# mcu.net
KiCad netlist of a schematic drawn in Altium Designer
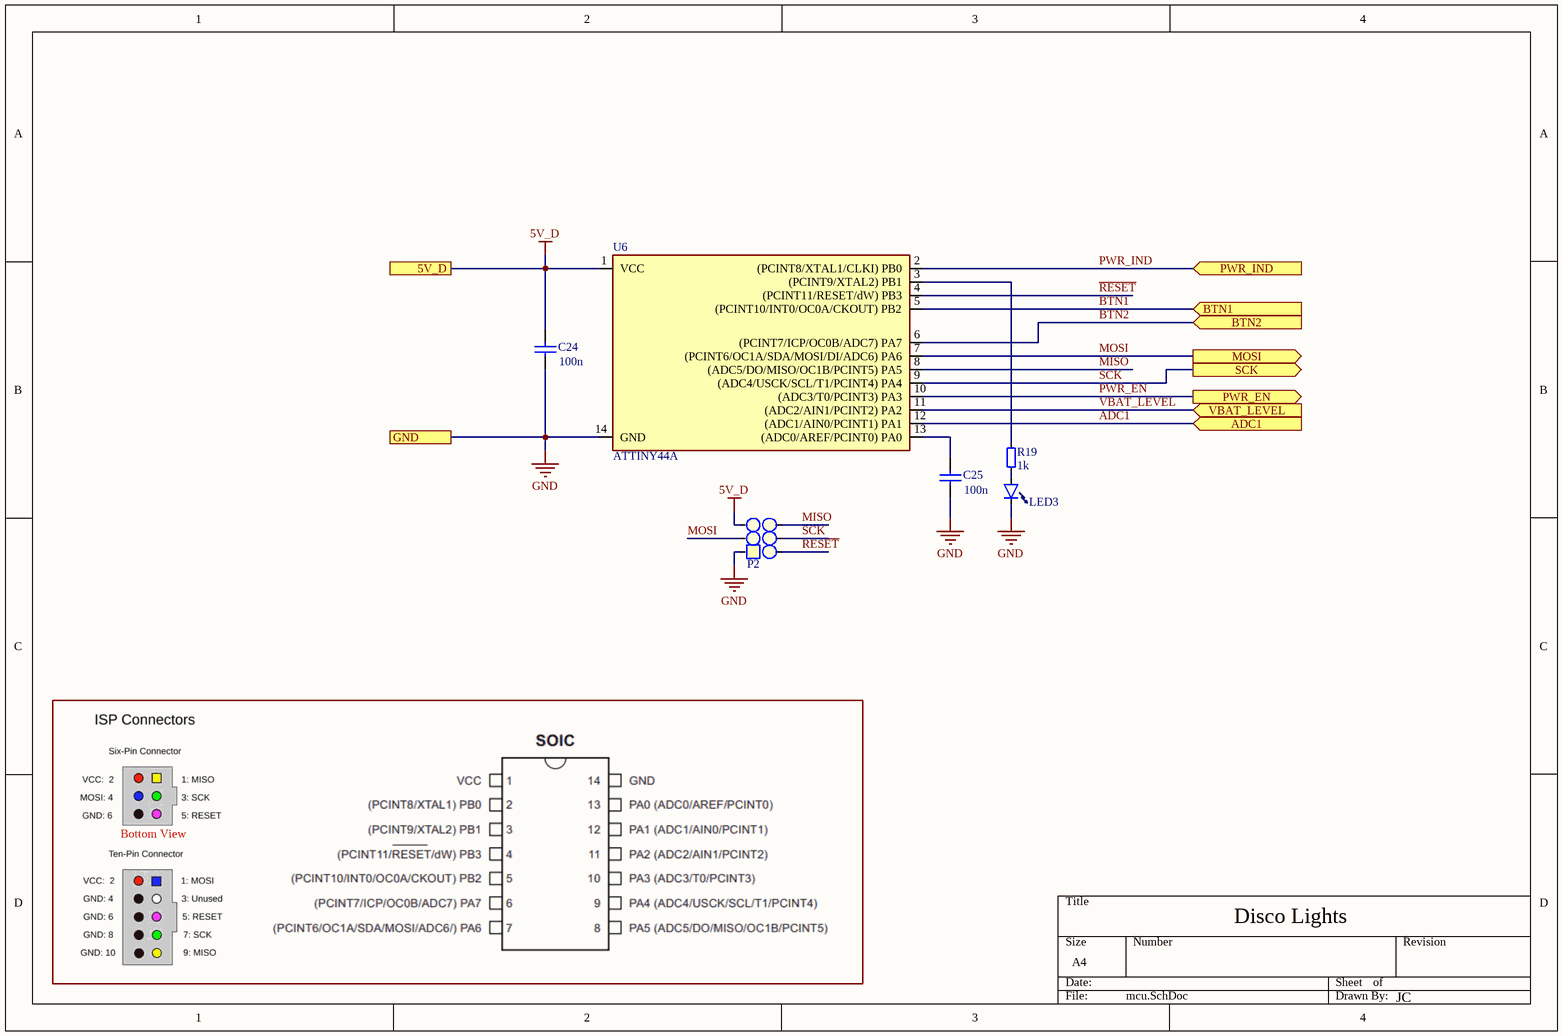
[diagram p0: mcu.SchDoc]

(export (version "E")
  (design (tool "Eeschema 10.0.6"))
  (components
    (comp (ref "C24")
      (value "100n")
      (footprint "MMK7.5104K100K00L4BULK")
      (fields (field (name "Comment") "CAP, TH"))
      (libsource (lib "urad") (part "CAP, TH"))
    )
    (comp (ref "C25")
      (value "100n")
      (footprint "MMK7.5104K100K00L4BULK")
      (fields (field (name "Comment") "CAP, TH"))
      (libsource (lib "urad") (part "CAP, TH"))
    )
    (comp (ref "LED3")
      (value "0805, LED")
      (footprint "0805_led")
      (fields
        (field (name "JLCPCB PART #") "C598285")
        (field (name "MANUFACTURER PART NUMBER") "KP-2012SURCK")
      )
      (libsource (lib "jclib") (part "0805, LED"))
    )
    (comp (ref "P2")
      (value "2x3 Pin Header")
      (footprint "2x3 PH")
      (libsource (lib "jclib") (part "2x3 Pin Header"))
    )
    (comp (ref "R19")
      (value "1k")
      (footprint "0603")
      (fields
        (field (name "JLCPCB PART #") "C203217")
        (field (name "MANUFACTURER PART NUMBER") "CR0603-FX-1001ELF")
        (field (name "Comment") "0603, resistor")
      )
      (libsource (lib "jclib") (part "0603, resistor"))
    )
    (comp (ref "U6")
      (value "ATTINY44A")
      (footprint "DIP14")
      (description "8-bit microcontrollers based on the AVR® enhanced RISC\r\narchitecture.")
      (libsource (lib "jclib") (part "ATTINY44A"))
    )
  )
  (nets
    (net (code "1") (name "/ADC1") (class "Default")
      (node (ref "U6") (pin "12") (pinfunction "(ADC1/AIN0/PCINT1)_PA1_12") (pintype "passive"))
    )
    (net (code "2") (name "/BTN1") (class "Default")
      (node (ref "U6") (pin "5") (pinfunction "(PCINT10/INT0/OC0A/CKOUT)_PB2_5") (pintype "passive"))
    )
    (net (code "3") (name "/BTN2") (class "Default")
      (node (ref "U6") (pin "6") (pinfunction "(PCINT7/ICP/OC0B/ADC7)_PA7_6") (pintype "passive"))
    )
    (net (code "4") (name "/MISO") (class "Default")
      (node (ref "P2") (pin "4") (pinfunction "4_4") (pintype "passive"))
      (node (ref "U6") (pin "8") (pinfunction "(ADC5/DO/MISO/OC1B/PCINT5)_PA5_8") (pintype "passive"))
    )
    (net (code "5") (name "/MOSI") (class "Default")
      (node (ref "P2") (pin "2") (pinfunction "2_2") (pintype "passive"))
      (node (ref "U6") (pin "7") (pinfunction "(PCINT6/OC1A/SDA/MOSI/DI/ADC6)_PA6_7") (pintype "passive"))
    )
    (net (code "6") (name "/PWR_EN") (class "Default")
      (node (ref "U6") (pin "10") (pinfunction "(ADC3/T0/PCINT3)_PA3_10") (pintype "passive"))
    )
    (net (code "7") (name "/PWR_IND") (class "Default")
      (node (ref "U6") (pin "2") (pinfunction "(PCINT8/XTAL1/CLKI)_PB0_2") (pintype "passive"))
    )
    (net (code "8") (name "/SCK") (class "Default")
      (node (ref "P2") (pin "5") (pinfunction "5_5") (pintype "passive"))
      (node (ref "U6") (pin "9") (pinfunction "(ADC4/USCK/SCL/T1/PCINT4)_PA4_9") (pintype "passive"))
    )
    (net (code "9") (name "/VBAT_LEVEL") (class "Default")
      (node (ref "U6") (pin "11") (pinfunction "(ADC2/AIN1/PCINT2)_PA2_11") (pintype "passive"))
    )
    (net (code "10") (name "/~{RESET}") (class "Default")
      (node (ref "P2") (pin "6") (pinfunction "6_6") (pintype "passive"))
      (node (ref "U6") (pin "4") (pinfunction "(PCINT11/RESET/dW)_PB3_4") (pintype "passive"))
    )
    (net (code "11") (name "5V_D") (class "Default")
      (node (ref "C24") (pin "1") (pinfunction "1_1") (pintype "passive"))
      (node (ref "P2") (pin "3") (pinfunction "3_3") (pintype "passive"))
      (node (ref "U6") (pin "1") (pinfunction "VCC_1") (pintype "passive"))
    )
    (net (code "12") (name "GND") (class "Default")
      (node (ref "C24") (pin "2") (pinfunction "2_2") (pintype "passive"))
      (node (ref "C25") (pin "2") (pinfunction "2_2") (pintype "passive"))
      (node (ref "LED3") (pin "0") (pinfunction "Cathode_0") (pintype "passive"))
      (node (ref "P2") (pin "1") (pinfunction "1_1") (pintype "passive"))
      (node (ref "U6") (pin "14") (pinfunction "GND_14") (pintype "passive"))
    )
    (net (code "13") (name "Net-(LED3-Pad1)") (class "Default")
      (node (ref "LED3") (pin "1") (pinfunction "1_1") (pintype "passive"))
      (node (ref "R19") (pin "0") (pinfunction "0_0") (pintype "passive"))
    )
    (net (code "14") (name "Net-(U6-(ADC0{slash}AREF{slash}PCINT0)_PA0)") (class "Default")
      (node (ref "C25") (pin "1") (pinfunction "1_1") (pintype "passive"))
      (node (ref "U6") (pin "13") (pinfunction "(ADC0/AREF/PCINT0)_PA0_13") (pintype "passive"))
    )
    (net (code "15") (name "Net-(U6-(PCINT9{slash}XTAL2)_PB1)") (class "Default")
      (node (ref "R19") (pin "1") (pinfunction "1_1") (pintype "passive"))
      (node (ref "U6") (pin "3") (pinfunction "(PCINT9/XTAL2)_PB1_3") (pintype "passive"))
    )
  )
)
